# untitled.net
KiCad netlist of a schematic drawn in EAGLE
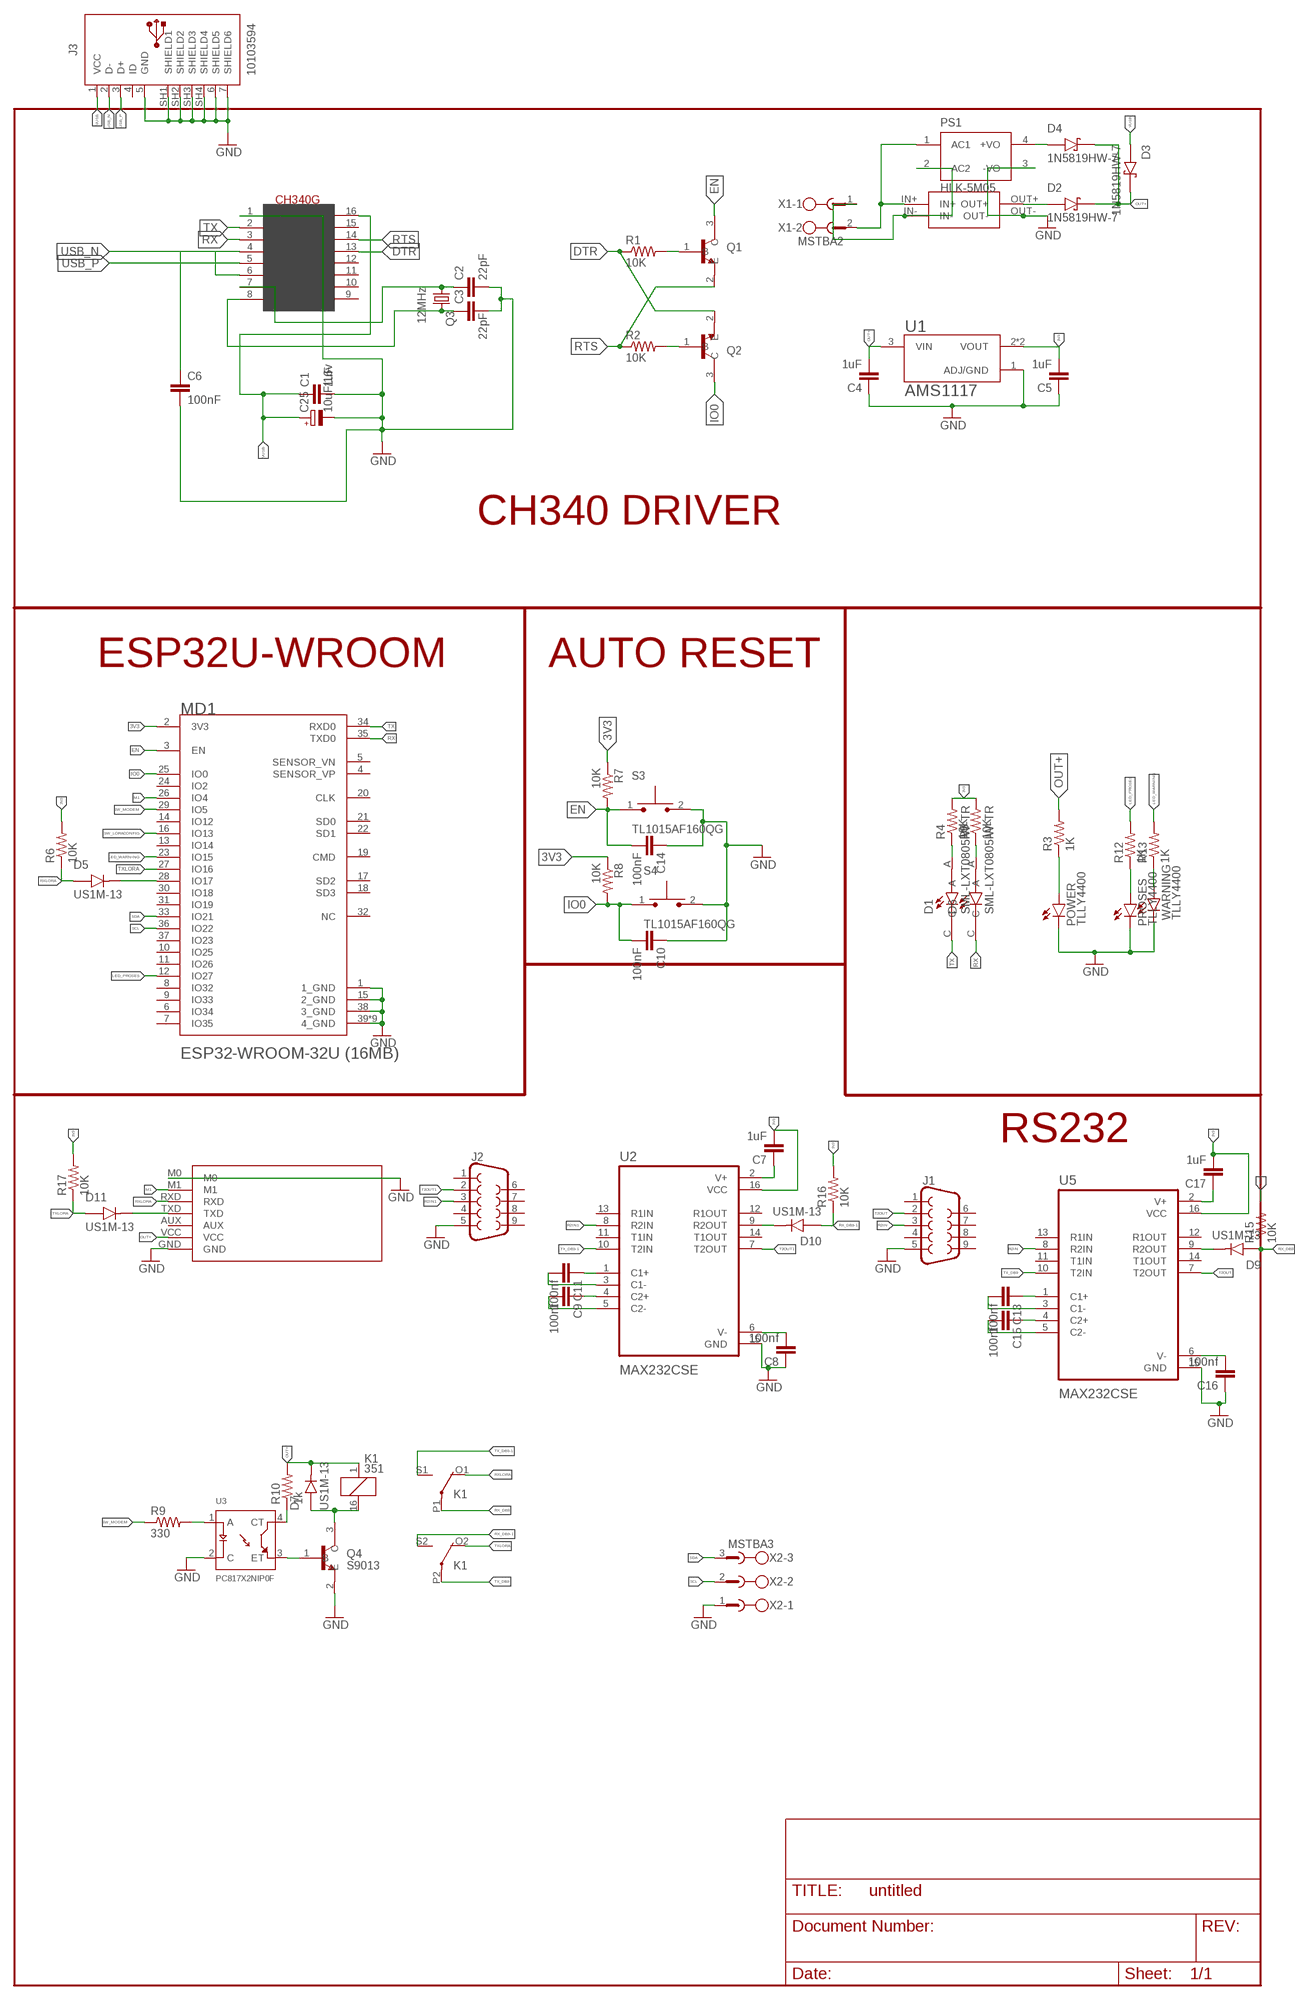
[diagram p0: schematic, sheet 1]

(export (version "E")
  (design (tool "Eeschema 10.0.6"))
  (components
    (comp (ref "C1")
      (value "1uF")
      (footprint "eagle-import:C0805K")
      (libsource (lib "eagle-import") (part "C-EUC0805K"))
    )
    (comp (ref "C2")
      (value "22pF")
      (footprint "eagle-import:C0805K")
      (libsource (lib "eagle-import") (part "C-EUC0805K"))
    )
    (comp (ref "C3")
      (value "22pF")
      (footprint "eagle-import:C0805K")
      (libsource (lib "eagle-import") (part "C-EUC0805K"))
    )
    (comp (ref "C4")
      (value "1uF")
      (footprint "eagle-import:C0805K")
      (libsource (lib "eagle-import") (part "C-EUC0805K"))
    )
    (comp (ref "C5")
      (value "1uF")
      (footprint "eagle-import:C0805K")
      (libsource (lib "eagle-import") (part "C-EUC0805K"))
    )
    (comp (ref "C6")
      (value "100nF")
      (footprint "eagle-import:C0805K")
      (libsource (lib "eagle-import") (part "C-EUC0805K"))
    )
    (comp (ref "C7")
      (value "1uF")
      (footprint "eagle-import:C0805")
      (libsource (lib "eagle-import") (part "C-EUC0805"))
    )
    (comp (ref "C8")
      (value "100nf")
      (footprint "eagle-import:C0805")
      (libsource (lib "eagle-import") (part "C-EUC0805"))
    )
    (comp (ref "C9")
      (value "100nf")
      (footprint "eagle-import:C0805")
      (libsource (lib "eagle-import") (part "C-EUC0805"))
    )
    (comp (ref "C10")
      (value "100nF")
      (footprint "eagle-import:C0805K")
      (libsource (lib "eagle-import") (part "C-EUC0805K"))
    )
    (comp (ref "C11")
      (value "100nf")
      (footprint "eagle-import:C0805")
      (libsource (lib "eagle-import") (part "C-EUC0805"))
    )
    (comp (ref "C13")
      (value "100nf")
      (footprint "eagle-import:C0805")
      (libsource (lib "eagle-import") (part "C-EUC0805"))
    )
    (comp (ref "C14")
      (value "100nF")
      (footprint "eagle-import:C0805K")
      (libsource (lib "eagle-import") (part "C-EUC0805K"))
    )
    (comp (ref "C15")
      (value "100nf")
      (footprint "eagle-import:C0805")
      (libsource (lib "eagle-import") (part "C-EUC0805"))
    )
    (comp (ref "C16")
      (value "100nf")
      (footprint "eagle-import:C0805")
      (libsource (lib "eagle-import") (part "C-EUC0805"))
    )
    (comp (ref "C17")
      (value "1uF")
      (footprint "eagle-import:C0805")
      (libsource (lib "eagle-import") (part "C-EUC0805"))
    )
    (comp (ref "C25")
      (value "10uF/16v")
      (footprint "eagle-import:153CLV-0505")
      (libsource (lib "eagle-import") (part "CPOL-EU153CLV-0505"))
    )
    (comp (ref "D1")
      (value "SML-LXT0805IW-TR")
      (footprint "eagle-import:LEDC2012X120N")
      (fields (field (name "MF") "Lumex Opto/Components"))
      (libsource (lib "eagle-import") (part "SML-LXT0805IW-TR"))
    )
    (comp (ref "D2")
      (value "1N5819HW-7")
      (footprint "eagle-import:SOD3715X145N")
      (fields (field (name "MF") "Diodes Inc."))
      (libsource (lib "eagle-import") (part "1N5819HW-7"))
    )
    (comp (ref "D3")
      (value "1N5819HW-7")
      (footprint "eagle-import:SOD3715X145N")
      (fields (field (name "MF") "Diodes Inc."))
      (libsource (lib "eagle-import") (part "1N5819HW-7"))
    )
    (comp (ref "D4")
      (value "1N5819HW-7")
      (footprint "eagle-import:SOD3715X145N")
      (fields (field (name "MF") "Diodes Inc."))
      (libsource (lib "eagle-import") (part "1N5819HW-7"))
    )
    (comp (ref "D5")
      (value "US1M-13")
      (footprint "eagle-import:DIOM5226X240N")
      (fields (field (name "MF") "Diodes Incorporated"))
      (libsource (lib "eagle-import") (part "US1M-13"))
    )
    (comp (ref "D6")
      (value "SML-LXT0805IW-TR")
      (footprint "eagle-import:LEDC2012X120N")
      (fields (field (name "MF") "Lumex Opto/Components"))
      (libsource (lib "eagle-import") (part "SML-LXT0805IW-TR"))
    )
    (comp (ref "D7")
      (value "US1M-13")
      (footprint "eagle-import:DIOM5226X240N")
      (fields (field (name "MF") "Diodes Incorporated"))
      (libsource (lib "eagle-import") (part "US1M-13"))
    )
    (comp (ref "D9")
      (value "US1M-13")
      (footprint "eagle-import:DIOM5226X240N")
      (fields (field (name "MF") "Diodes Incorporated"))
      (libsource (lib "eagle-import") (part "US1M-13"))
    )
    (comp (ref "D10")
      (value "US1M-13")
      (footprint "eagle-import:DIOM5226X240N")
      (fields (field (name "MF") "Diodes Incorporated"))
      (libsource (lib "eagle-import") (part "US1M-13"))
    )
    (comp (ref "D11")
      (value "US1M-13")
      (footprint "eagle-import:DIOM5226X240N")
      (fields (field (name "MF") "Diodes Incorporated"))
      (libsource (lib "eagle-import") (part "US1M-13"))
    )
    (comp (ref "EBYTEE220-900T22D1")
      (value "EBYTEE220-900T22D")
      (footprint "eagle-import:EBYTEE220-900T22D")
      (libsource (lib "eagle-import") (part "EBYTEE220-900T22D"))
    )
    (comp (ref "J1")
      (value "DB9MALE")
      (footprint "eagle-import:DB9_MALE")
      (libsource (lib "eagle-import") (part "DB9MALE"))
    )
    (comp (ref "J2")
      (value "DB9MALE")
      (footprint "eagle-import:DB9_MALE")
      (libsource (lib "eagle-import") (part "DB9MALE"))
    )
    (comp (ref "J3")
      (value "10103594")
      (footprint "eagle-import:10103594")
      (fields (field (name "MANUFACTURER") "Amphenol ICC (FCI)") (field (name "MPN") "10103594-0001LF"))
      (libsource (lib "eagle-import") (part "10103594"))
    )
    (comp (ref "K1")
      (value "351")
      (footprint "eagle-import:351")
      (libsource (lib "eagle-import") (part "351"))
    )
    (comp (ref "MD1")
      (value "ESPRESSIF_SYSTEMS_ESP32-WROOM-32U_16MBESPRESSIF_SYSTEMS_ESP32-WROOM-32U_16MB_0_0")
      (footprint "eagle-import:ESPRESSIF_SYSTEMS_ESP32-WROOM-32U_16MB_0")
      (fields
        (field (name "DIGIKEY_PART_NUMBER") "1904-1028-1-ND")
        (field (name "MF") "Espressif Systems")
        (field (name "MOUSER_PART_NUMBER") "356-ES32WROOM32U16MB")
      )
      (libsource (lib "eagle-import") (part "ESPRESSIF_SYSTEMS_ESP32-WROOM-32U_16MBESPRESSIF_SYSTEMS_ESP32-WROOM-32U_16MB_0_0"))
    )
    (comp (ref "MINI1")
      (value "MINI560")
      (footprint "eagle-import:MINI560")
      (libsource (lib "eagle-import") (part "MINI560"))
    )
    (comp (ref "POWER")
      (value "TLLY4400")
      (footprint "eagle-import:LED3MM")
      (fields (field (name "MF") "VISHAY SEMICONDUCTOR"))
      (libsource (lib "eagle-import") (part "TLLY4400"))
    )
    (comp (ref "PROSES")
      (value "TLLY4400")
      (footprint "eagle-import:LED3MM")
      (fields (field (name "MF") "VISHAY SEMICONDUCTOR"))
      (libsource (lib "eagle-import") (part "TLLY4400"))
    )
    (comp (ref "PS1")
      (value "HLK-5M05")
      (footprint "eagle-import:CONV_HLK-5M05")
      (fields (field (name "MF") "Hi-link"))
      (libsource (lib "eagle-import") (part "HLK-5M05"))
    )
    (comp (ref "Q1")
      (value "MMBT3904")
      (footprint "eagle-import:SOT95P240X120-3N")
      (fields (field (name "MF") "STMicroelectronics"))
      (libsource (lib "eagle-import") (part "MMBT3904"))
    )
    (comp (ref "Q2")
      (value "MMBT3904")
      (footprint "eagle-import:SOT95P240X120-3N")
      (fields (field (name "MF") "STMicroelectronics"))
      (libsource (lib "eagle-import") (part "MMBT3904"))
    )
    (comp (ref "Q3")
      (value "12MHz")
      (footprint "eagle-import:SM49")
      (libsource (lib "eagle-import") (part "CRYSTALSM49"))
    )
    (comp (ref "Q4")
      (value "S9013")
      (footprint "eagle-import:SOT95P240X120-3N")
      (fields (field (name "MF") "JCET"))
      (libsource (lib "eagle-import") (part "S9013"))
    )
    (comp (ref "R1")
      (value "10K")
      (footprint "eagle-import:M0805")
      (libsource (lib "eagle-import") (part "R-US_M0805"))
    )
    (comp (ref "R2")
      (value "10K")
      (footprint "eagle-import:M0805")
      (libsource (lib "eagle-import") (part "R-US_M0805"))
    )
    (comp (ref "R3")
      (value "1K")
      (footprint "eagle-import:M0805")
      (libsource (lib "eagle-import") (part "R-US_M0805"))
    )
    (comp (ref "R4")
      (value "10K")
      (footprint "eagle-import:M0805")
      (libsource (lib "eagle-import") (part "R-US_M0805"))
    )
    (comp (ref "R5")
      (value "10K")
      (footprint "eagle-import:M0805")
      (libsource (lib "eagle-import") (part "R-US_M0805"))
    )
    (comp (ref "R6")
      (value "10K")
      (footprint "eagle-import:M0805")
      (libsource (lib "eagle-import") (part "R-US_M0805"))
    )
    (comp (ref "R7")
      (value "10K")
      (footprint "eagle-import:M0805")
      (libsource (lib "eagle-import") (part "R-US_M0805"))
    )
    (comp (ref "R8")
      (value "10K")
      (footprint "eagle-import:M0805")
      (libsource (lib "eagle-import") (part "R-US_M0805"))
    )
    (comp (ref "R9")
      (value "330")
      (footprint "eagle-import:M0805")
      (libsource (lib "eagle-import") (part "R-US_M0805"))
    )
    (comp (ref "R10")
      (value "1k")
      (footprint "eagle-import:M0805")
      (libsource (lib "eagle-import") (part "R-US_M0805"))
    )
    (comp (ref "R12")
      (value "1K")
      (footprint "eagle-import:M0805")
      (libsource (lib "eagle-import") (part "R-US_M0805"))
    )
    (comp (ref "R13")
      (value "1K")
      (footprint "eagle-import:M0805")
      (libsource (lib "eagle-import") (part "R-US_M0805"))
    )
    (comp (ref "R15")
      (value "10K")
      (footprint "eagle-import:M0805")
      (libsource (lib "eagle-import") (part "R-US_M0805"))
    )
    (comp (ref "R16")
      (value "10K")
      (footprint "eagle-import:M0805")
      (libsource (lib "eagle-import") (part "R-US_M0805"))
    )
    (comp (ref "R17")
      (value "10K")
      (footprint "eagle-import:M0805")
      (libsource (lib "eagle-import") (part "R-US_M0805"))
    )
    (comp (ref "S3")
      (value "TL1015AF160QG")
      (footprint "eagle-import:SW_TL1015AF160QG")
      (fields (field (name "MF") "E-Switch"))
      (libsource (lib "eagle-import") (part "TL1015AF160QG"))
    )
    (comp (ref "S4")
      (value "TL1015AF160QG")
      (footprint "eagle-import:SW_TL1015AF160QG")
      (fields (field (name "MF") "E-Switch"))
      (libsource (lib "eagle-import") (part "TL1015AF160QG"))
    )
    (comp (ref "U$2")
      (value "CH340G")
      (footprint "eagle-import:SOIC16")
      (libsource (lib "eagle-import") (part "CH340G"))
    )
    (comp (ref "U1")
      (value "AMS1117")
      (footprint "eagle-import:SOT229P700X180-4N")
      (fields (field (name "MF") "Advanced Monolithic Systems"))
      (libsource (lib "eagle-import") (part "AMS1117"))
    )
    (comp (ref "U2")
      (value "MAX232CSE")
      (footprint "eagle-import:SOIC127P600X175-16N")
      (fields (field (name "MF") "Maxim Integrated"))
      (libsource (lib "eagle-import") (part "MAX232CSE"))
    )
    (comp (ref "U3")
      (value "PC817X2NIP0F")
      (footprint "eagle-import:SOT254P975X400-4N")
      (fields (field (name "MF") "Sharp Microelectronics"))
      (libsource (lib "eagle-import") (part "PC817X2NIP0F"))
    )
    (comp (ref "U5")
      (value "MAX232CSE")
      (footprint "eagle-import:SOIC127P600X175-16N")
      (fields (field (name "MF") "Maxim Integrated"))
      (libsource (lib "eagle-import") (part "MAX232CSE"))
    )
    (comp (ref "WARNING")
      (value "TLLY4400")
      (footprint "eagle-import:LED3MM")
      (fields (field (name "MF") "VISHAY SEMICONDUCTOR"))
      (libsource (lib "eagle-import") (part "TLLY4400"))
    )
    (comp (ref "X1")
      (value "MSTBA2")
      (footprint "eagle-import:MSTBA2")
      (fields (field (name "MF") "FARNELL") (field (name "MPN") "1757242"))
      (libsource (lib "eagle-import") (part "MSTBA2"))
    )
    (comp (ref "X2")
      (value "MSTBA3")
      (footprint "eagle-import:MSTBA3")
      (fields (field (name "MF") "FARNELL") (field (name "MPN") "1757255"))
      (libsource (lib "eagle-import") (part "MSTBA3"))
    )
  )
  (nets
    (net (code "1") (name "3V3") (class "Default")
      (node (ref "C17") (pin "2") (pinfunction "2_2") (pintype "passive"))
      (node (ref "C5") (pin "2") (pinfunction "2_2") (pintype "passive"))
      (node (ref "C7") (pin "2") (pinfunction "2_2") (pintype "passive"))
      (node (ref "MD1") (pin "2") (pinfunction "3V3_2") (pintype "power_in"))
      (node (ref "R15") (pin "2") (pinfunction "2_2") (pintype "passive"))
      (node (ref "R16") (pin "2") (pinfunction "2_2") (pintype "passive"))
      (node (ref "R17") (pin "2") (pinfunction "2_2") (pintype "passive"))
      (node (ref "R4") (pin "2") (pinfunction "2_2") (pintype "passive"))
      (node (ref "R5") (pin "2") (pinfunction "2_2") (pintype "passive"))
      (node (ref "R6") (pin "2") (pinfunction "2_2") (pintype "passive"))
      (node (ref "R7") (pin "1") (pinfunction "1_1") (pintype "passive"))
      (node (ref "R8") (pin "1") (pinfunction "1_1") (pintype "passive"))
      (node (ref "U1") (pin "2") (pinfunction "VOUT_2") (pintype "output"))
      (node (ref "U1") (pin "4") (pinfunction "VOUT_4") (pintype "output"))
      (node (ref "U2") (pin "16") (pinfunction "VCC_16") (pintype "power_in"))
      (node (ref "U5") (pin "16") (pinfunction "VCC_16") (pintype "power_in"))
    )
    (net (code "2") (name "DTR") (class "Default")
      (node (ref "Q2") (pin "2") (pinfunction "E_2") (pintype "passive"))
      (node (ref "R1") (pin "1") (pinfunction "1_1") (pintype "passive"))
      (node (ref "U$2") (pin "13") (pinfunction "DTR_13") (pintype "bidirectional"))
    )
    (net (code "3") (name "EN") (class "Default")
      (node (ref "C14") (pin "2") (pinfunction "2_2") (pintype "passive"))
      (node (ref "MD1") (pin "3") (pinfunction "EN_3") (pintype "input"))
      (node (ref "Q1") (pin "3") (pinfunction "C_3") (pintype "passive"))
      (node (ref "R7") (pin "2") (pinfunction "2_2") (pintype "passive"))
      (node (ref "S3") (pin "1") (pinfunction "1_1") (pintype "passive"))
    )
    (net (code "4") (name "GND") (class "Default")
      (node (ref "C1") (pin "2") (pinfunction "2_2") (pintype "passive"))
      (node (ref "C10") (pin "1") (pinfunction "1_1") (pintype "passive"))
      (node (ref "C14") (pin "1") (pinfunction "1_1") (pintype "passive"))
      (node (ref "C16") (pin "1") (pinfunction "1_1") (pintype "passive"))
      (node (ref "C2") (pin "2") (pinfunction "2_2") (pintype "passive"))
      (node (ref "C25") (pin "-") (pinfunction "-_-") (pintype "passive"))
      (node (ref "C3") (pin "2") (pinfunction "2_2") (pintype "passive"))
      (node (ref "C4") (pin "1") (pinfunction "1_1") (pintype "passive"))
      (node (ref "C5") (pin "1") (pinfunction "1_1") (pintype "passive"))
      (node (ref "C6") (pin "2") (pinfunction "2_2") (pintype "passive"))
      (node (ref "C8") (pin "1") (pinfunction "1_1") (pintype "passive"))
      (node (ref "EBYTEE220-900T22D1") (pin "GND") (pinfunction "GND_GND") (pintype "bidirectional"))
      (node (ref "EBYTEE220-900T22D1") (pin "M0") (pinfunction "M0_M0") (pintype "bidirectional"))
      (node (ref "J1") (pin "5") (pinfunction "5_5") (pintype "passive"))
      (node (ref "J2") (pin "5") (pinfunction "5_5") (pintype "passive"))
      (node (ref "J3") (pin "5") (pinfunction "GND_5") (pintype "power_in"))
      (node (ref "J3") (pin "6") (pinfunction "SHIELD5_6") (pintype "power_in"))
      (node (ref "J3") (pin "7") (pinfunction "SHIELD6_7") (pintype "power_in"))
      (node (ref "J3") (pin "SH1") (pinfunction "SHIELD1_SH1") (pintype "power_in"))
      (node (ref "J3") (pin "SH2") (pinfunction "SHIELD2_SH2") (pintype "power_in"))
      (node (ref "J3") (pin "SH3") (pinfunction "SHIELD3_SH3") (pintype "power_in"))
      (node (ref "J3") (pin "SH4") (pinfunction "SHIELD4_SH4") (pintype "power_in"))
      (node (ref "MD1") (pin "1") (pinfunction "1_GND_1") (pintype "power_in"))
      (node (ref "MD1") (pin "15") (pinfunction "2_GND_15") (pintype "power_in"))
      (node (ref "MD1") (pin "38") (pinfunction "3_GND_38") (pintype "power_in"))
      (node (ref "MD1") (pin "39") (pinfunction "4_GND_39") (pintype "power_in"))
      (node (ref "MD1") (pin "39-2") (pinfunction "4_GND_39-2") (pintype "power_in"))
      (node (ref "MD1") (pin "39-3") (pinfunction "4_GND_39-3") (pintype "power_in"))
      (node (ref "MD1") (pin "39-4") (pinfunction "4_GND_39-4") (pintype "power_in"))
      (node (ref "MD1") (pin "39-5") (pinfunction "4_GND_39-5") (pintype "power_in"))
      (node (ref "MD1") (pin "39-6") (pinfunction "4_GND_39-6") (pintype "power_in"))
      (node (ref "MD1") (pin "39-7") (pinfunction "4_GND_39-7") (pintype "power_in"))
      (node (ref "MD1") (pin "39-8") (pinfunction "4_GND_39-8") (pintype "power_in"))
      (node (ref "MD1") (pin "39-9") (pinfunction "4_GND_39-9") (pintype "power_in"))
      (node (ref "MINI1") (pin "OUT-") (pinfunction "OUT-_OUT-") (pintype "bidirectional"))
      (node (ref "POWER") (pin "K") (pinfunction "C_K") (pintype "passive"))
      (node (ref "PROSES") (pin "K") (pinfunction "C_K") (pintype "passive"))
      (node (ref "PS1") (pin "3") (pinfunction "-VO_3") (pintype "output"))
      (node (ref "Q4") (pin "2") (pinfunction "E_2") (pintype "passive"))
      (node (ref "S3") (pin "2") (pinfunction "2_2") (pintype "passive"))
      (node (ref "S4") (pin "2") (pinfunction "2_2") (pintype "passive"))
      (node (ref "U$2") (pin "1") (pinfunction "GND_1") (pintype "bidirectional"))
      (node (ref "U1") (pin "1") (pinfunction "ADJ/GND_1") (pintype "power_in"))
      (node (ref "U2") (pin "15") (pinfunction "GND_15") (pintype "power_in"))
      (node (ref "U3") (pin "2") (pinfunction "C_2") (pintype "passive"))
      (node (ref "U5") (pin "15") (pinfunction "GND_15") (pintype "power_in"))
      (node (ref "WARNING") (pin "K") (pinfunction "C_K") (pintype "passive"))
      (node (ref "X2") (pin "1") (pinfunction "1_1") (pintype "passive"))
    )
    (net (code "5") (name "IO0") (class "Default")
      (node (ref "C10") (pin "2") (pinfunction "2_2") (pintype "passive"))
      (node (ref "MD1") (pin "25") (pinfunction "IO0_25") (pintype "bidirectional"))
      (node (ref "Q2") (pin "3") (pinfunction "C_3") (pintype "passive"))
      (node (ref "R8") (pin "2") (pinfunction "2_2") (pintype "passive"))
      (node (ref "S4") (pin "1") (pinfunction "1_1") (pintype "passive"))
    )
    (net (code "6") (name "LED_PROSES") (class "Default")
      (node (ref "MD1") (pin "12") (pinfunction "IO27_12") (pintype "bidirectional"))
      (node (ref "R12") (pin "2") (pinfunction "2_2") (pintype "passive"))
    )
    (net (code "7") (name "LED_WARNING") (class "Default")
      (node (ref "MD1") (pin "23") (pinfunction "IO15_23") (pintype "bidirectional"))
      (node (ref "R13") (pin "2") (pinfunction "2_2") (pintype "passive"))
    )
    (net (code "8") (name "M1") (class "Default")
      (node (ref "EBYTEE220-900T22D1") (pin "M1") (pinfunction "M1_M1") (pintype "bidirectional"))
      (node (ref "MD1") (pin "26") (pinfunction "IO4_26") (pintype "bidirectional"))
    )
    (net (code "9") (name "Net-(D1-PadA)") (class "Default")
      (node (ref "D1") (pin "A") (pinfunction "A_A") (pintype "passive"))
      (node (ref "R4") (pin "1") (pinfunction "1_1") (pintype "passive"))
    )
    (net (code "10") (name "Net-(D2-PadA)") (class "Default")
      (node (ref "D2") (pin "A") (pinfunction "A_A") (pintype "passive"))
      (node (ref "MINI1") (pin "OUT+") (pinfunction "OUT+_OUT+") (pintype "bidirectional"))
    )
    (net (code "11") (name "Net-(D5-K)") (class "Default")
      (node (ref "D5") (pin "C") (pinfunction "K_C") (pintype "passive"))
      (node (ref "MD1") (pin "28") (pinfunction "IO17_28") (pintype "bidirectional"))
    )
    (net (code "12") (name "Net-(D6-PadA)") (class "Default")
      (node (ref "D6") (pin "A") (pinfunction "A_A") (pintype "passive"))
      (node (ref "R5") (pin "1") (pinfunction "1_1") (pintype "passive"))
    )
    (net (code "13") (name "Net-(D9-K)") (class "Default")
      (node (ref "D9") (pin "C") (pinfunction "K_C") (pintype "passive"))
      (node (ref "U5") (pin "9") (pinfunction "R2OUT_9") (pintype "output"))
    )
    (net (code "14") (name "Net-(D10-K)") (class "Default")
      (node (ref "D10") (pin "C") (pinfunction "K_C") (pintype "passive"))
      (node (ref "U2") (pin "9") (pinfunction "R2OUT_9") (pintype "output"))
    )
    (net (code "15") (name "Net-(D11-K)") (class "Default")
      (node (ref "D11") (pin "C") (pinfunction "K_C") (pintype "passive"))
      (node (ref "EBYTEE220-900T22D1") (pin "TXD") (pinfunction "TXD_TXD") (pintype "bidirectional"))
    )
    (net (code "16") (name "Net-(K1A-2)") (class "Default")
      (node (ref "D7") (pin "A") (pinfunction "A_A") (pintype "passive"))
      (node (ref "K1") (pin "16") (pinfunction "2_16") (pintype "passive"))
      (node (ref "Q4") (pin "3") (pinfunction "C_3") (pintype "passive"))
    )
    (net (code "17") (name "Net-(POWER-PadA)") (class "Default")
      (node (ref "POWER") (pin "A") (pinfunction "A_A") (pintype "passive"))
      (node (ref "R3") (pin "1") (pinfunction "1_1") (pintype "passive"))
    )
    (net (code "18") (name "Net-(PROSES-PadA)") (class "Default")
      (node (ref "PROSES") (pin "A") (pinfunction "A_A") (pintype "passive"))
      (node (ref "R12") (pin "1") (pinfunction "1_1") (pintype "passive"))
    )
    (net (code "19") (name "Net-(PS1-+VO)") (class "Default")
      (node (ref "D4") (pin "A") (pinfunction "A_A") (pintype "passive"))
      (node (ref "PS1") (pin "4") (pinfunction "+VO_4") (pintype "output"))
    )
    (net (code "20") (name "Net-(PS1-AC1)") (class "Default")
      (node (ref "MINI1") (pin "IN+") (pinfunction "IN+_IN+") (pintype "bidirectional"))
      (node (ref "PS1") (pin "1") (pinfunction "AC1_1") (pintype "input"))
      (node (ref "X1") (pin "2") (pinfunction "1_2") (pintype "passive"))
    )
    (net (code "21") (name "Net-(PS1-AC2)") (class "Default")
      (node (ref "MINI1") (pin "IN-") (pinfunction "IN-_IN-") (pintype "bidirectional"))
      (node (ref "PS1") (pin "2") (pinfunction "AC2_2") (pintype "input"))
      (node (ref "X1") (pin "1") (pinfunction "1_1") (pintype "passive"))
    )
    (net (code "22") (name "Net-(Q1-B)") (class "Default")
      (node (ref "Q1") (pin "1") (pinfunction "B_1") (pintype "passive"))
      (node (ref "R1") (pin "2") (pinfunction "2_2") (pintype "passive"))
    )
    (net (code "23") (name "Net-(Q2-B)") (class "Default")
      (node (ref "Q2") (pin "1") (pinfunction "B_1") (pintype "passive"))
      (node (ref "R2") (pin "2") (pinfunction "2_2") (pintype "passive"))
    )
    (net (code "24") (name "Net-(Q4-B)") (class "Default")
      (node (ref "Q4") (pin "1") (pinfunction "B_1") (pintype "passive"))
      (node (ref "U3") (pin "3") (pinfunction "ET_3") (pintype "passive"))
    )
    (net (code "25") (name "Net-(R13-Pad1)") (class "Default")
      (node (ref "R13") (pin "1") (pinfunction "1_1") (pintype "passive"))
      (node (ref "WARNING") (pin "A") (pinfunction "A_A") (pintype "passive"))
    )
    (net (code "26") (name "Net-(U$2-V3)") (class "Default")
      (node (ref "C6") (pin "1") (pinfunction "1_1") (pintype "passive"))
      (node (ref "U$2") (pin "4") (pinfunction "V3_4") (pintype "bidirectional"))
    )
    (net (code "27") (name "Net-(U$2-XI)") (class "Default")
      (node (ref "C2") (pin "1") (pinfunction "1_1") (pintype "passive"))
      (node (ref "Q3") (pin "1") (pinfunction "1_1") (pintype "passive"))
      (node (ref "U$2") (pin "7") (pinfunction "XI_7") (pintype "bidirectional"))
    )
    (net (code "28") (name "Net-(U$2-XO)") (class "Default")
      (node (ref "C3") (pin "1") (pinfunction "1_1") (pintype "passive"))
      (node (ref "Q3") (pin "2") (pinfunction "2_2") (pintype "passive"))
      (node (ref "U$2") (pin "8") (pinfunction "XO_8") (pintype "bidirectional"))
    )
    (net (code "29") (name "Net-(U2-C1+)") (class "Default")
      (node (ref "C11") (pin "1") (pinfunction "1_1") (pintype "passive"))
      (node (ref "U2") (pin "1") (pinfunction "C1+_1") (pintype "bidirectional"))
    )
    (net (code "30") (name "Net-(U2-C1-)") (class "Default")
      (node (ref "C11") (pin "2") (pinfunction "2_2") (pintype "passive"))
      (node (ref "U2") (pin "3") (pinfunction "C1-_3") (pintype "bidirectional"))
    )
    (net (code "31") (name "Net-(U2-C2+)") (class "Default")
      (node (ref "C9") (pin "1") (pinfunction "1_1") (pintype "passive"))
      (node (ref "U2") (pin "4") (pinfunction "C2+_4") (pintype "bidirectional"))
    )
    (net (code "32") (name "Net-(U2-C2-)") (class "Default")
      (node (ref "C9") (pin "2") (pinfunction "2_2") (pintype "passive"))
      (node (ref "U2") (pin "5") (pinfunction "C2-_5") (pintype "bidirectional"))
    )
    (net (code "33") (name "Net-(U2-V+)") (class "Default")
      (node (ref "C7") (pin "1") (pinfunction "1_1") (pintype "passive"))
      (node (ref "U2") (pin "2") (pinfunction "V+_2") (pintype "power_in"))
    )
    (net (code "34") (name "Net-(U2-V-)") (class "Default")
      (node (ref "C8") (pin "2") (pinfunction "2_2") (pintype "passive"))
      (node (ref "U2") (pin "6") (pinfunction "V-_6") (pintype "power_in"))
    )
    (net (code "35") (name "Net-(U3-A)") (class "Default")
      (node (ref "R9") (pin "2") (pinfunction "2_2") (pintype "passive"))
      (node (ref "U3") (pin "1") (pinfunction "A_1") (pintype "passive"))
    )
    (net (code "36") (name "Net-(U3-CT)") (class "Default")
      (node (ref "R10") (pin "1") (pinfunction "1_1") (pintype "passive"))
      (node (ref "U3") (pin "4") (pinfunction "CT_4") (pintype "passive"))
    )
    (net (code "37") (name "Net-(U5-C1+)") (class "Default")
      (node (ref "C13") (pin "1") (pinfunction "1_1") (pintype "passive"))
      (node (ref "U5") (pin "1") (pinfunction "C1+_1") (pintype "bidirectional"))
    )
    (net (code "38") (name "Net-(U5-C1-)") (class "Default")
      (node (ref "C13") (pin "2") (pinfunction "2_2") (pintype "passive"))
      (node (ref "U5") (pin "3") (pinfunction "C1-_3") (pintype "bidirectional"))
    )
    (net (code "39") (name "Net-(U5-C2+)") (class "Default")
      (node (ref "C15") (pin "1") (pinfunction "1_1") (pintype "passive"))
      (node (ref "U5") (pin "4") (pinfunction "C2+_4") (pintype "bidirectional"))
    )
    (net (code "40") (name "Net-(U5-C2-)") (class "Default")
      (node (ref "C15") (pin "2") (pinfunction "2_2") (pintype "passive"))
      (node (ref "U5") (pin "5") (pinfunction "C2-_5") (pintype "bidirectional"))
    )
    (net (code "41") (name "Net-(U5-V+)") (class "Default")
      (node (ref "C17") (pin "1") (pinfunction "1_1") (pintype "passive"))
      (node (ref "U5") (pin "2") (pinfunction "V+_2") (pintype "power_in"))
    )
    (net (code "42") (name "Net-(U5-V-)") (class "Default")
      (node (ref "C16") (pin "2") (pinfunction "2_2") (pintype "passive"))
      (node (ref "U5") (pin "6") (pinfunction "V-_6") (pintype "power_in"))
    )
    (net (code "43") (name "OUT+") (class "Default")
      (node (ref "C4") (pin "2") (pinfunction "2_2") (pintype "passive"))
      (node (ref "D2") (pin "C") (pinfunction "K_C") (pintype "passive"))
      (node (ref "D3") (pin "C") (pinfunction "K_C") (pintype "passive"))
      (node (ref "D4") (pin "C") (pinfunction "K_C") (pintype "passive"))
      (node (ref "D7") (pin "C") (pinfunction "K_C") (pintype "passive"))
      (node (ref "EBYTEE220-900T22D1") (pin "VCC") (pinfunction "VCC_VCC") (pintype "bidirectional"))
      (node (ref "K1") (pin "1") (pinfunction "1_1") (pintype "passive"))
      (node (ref "R10") (pin "2") (pinfunction "2_2") (pintype "passive"))
      (node (ref "R3") (pin "2") (pinfunction "2_2") (pintype "passive"))
      (node (ref "U1") (pin "3") (pinfunction "VIN_3") (pintype "input"))
    )
    (net (code "44") (name "R2IN") (class "Default")
      (node (ref "J1") (pin "3") (pinfunction "3_3") (pintype "passive"))
      (node (ref "U5") (pin "8") (pinfunction "R2IN_8") (pintype "input"))
    )
    (net (code "45") (name "R2IN1") (class "Default")
      (node (ref "J2") (pin "3") (pinfunction "3_3") (pintype "passive"))
      (node (ref "U2") (pin "8") (pinfunction "R2IN_8") (pintype "input"))
    )
    (net (code "46") (name "RTS") (class "Default")
      (node (ref "Q1") (pin "2") (pinfunction "E_2") (pintype "passive"))
      (node (ref "R2") (pin "1") (pinfunction "1_1") (pintype "passive"))
      (node (ref "U$2") (pin "14") (pinfunction "RTS_14") (pintype "bidirectional"))
    )
    (net (code "47") (name "RX") (class "Default")
      (node (ref "D6") (pin "C") (pinfunction "C_C") (pintype "passive"))
      (node (ref "MD1") (pin "35") (pinfunction "TXD0_35") (pintype "bidirectional"))
      (node (ref "U$2") (pin "3") (pinfunction "RX_3") (pintype "bidirectional"))
    )
    (net (code "48") (name "RXLORA") (class "Default")
      (node (ref "D5") (pin "A") (pinfunction "A_A") (pintype "passive"))
      (node (ref "EBYTEE220-900T22D1") (pin "RXD") (pinfunction "RXD_RXD") (pintype "bidirectional"))
      (node (ref "K1") (pin "O1") (pinfunction "O_O1") (pintype "passive"))
      (node (ref "R6") (pin "1") (pinfunction "1_1") (pintype "passive"))
    )
    (net (code "49") (name "RX_DB9") (class "Default")
      (node (ref "D9") (pin "A") (pinfunction "A_A") (pintype "passive"))
      (node (ref "K1") (pin "P1") (pinfunction "P_P1") (pintype "passive"))
      (node (ref "R15") (pin "1") (pinfunction "1_1") (pintype "passive"))
    )
    (net (code "50") (name "RX_DB9-1") (class "Default")
      (node (ref "D10") (pin "A") (pinfunction "A_A") (pintype "passive"))
      (node (ref "K1") (pin "S2") (pinfunction "S_S2") (pintype "passive"))
      (node (ref "R16") (pin "1") (pinfunction "1_1") (pintype "passive"))
    )
    (net (code "51") (name "SCL") (class "Default")
      (node (ref "MD1") (pin "36") (pinfunction "IO22_36") (pintype "bidirectional"))
      (node (ref "X2") (pin "2") (pinfunction "1_2") (pintype "passive"))
    )
    (net (code "52") (name "SDA") (class "Default")
      (node (ref "MD1") (pin "33") (pinfunction "IO21_33") (pintype "bidirectional"))
      (node (ref "X2") (pin "3") (pinfunction "1_3") (pintype "passive"))
    )
    (net (code "53") (name "SW_LORACONFIG") (class "Default")
      (node (ref "MD1") (pin "16") (pinfunction "IO13_16") (pintype "bidirectional"))
    )
    (net (code "54") (name "SW_MODEM") (class "Default")
      (node (ref "MD1") (pin "29") (pinfunction "IO5_29") (pintype "bidirectional"))
      (node (ref "R9") (pin "1") (pinfunction "1_1") (pintype "passive"))
    )
    (net (code "55") (name "T2OUT") (class "Default")
      (node (ref "J1") (pin "2") (pinfunction "2_2") (pintype "passive"))
      (node (ref "U5") (pin "7") (pinfunction "T2OUT_7") (pintype "output"))
    )
    (net (code "56") (name "T2OUT1") (class "Default")
      (node (ref "J2") (pin "2") (pinfunction "2_2") (pintype "passive"))
      (node (ref "U2") (pin "7") (pinfunction "T2OUT_7") (pintype "output"))
    )
    (net (code "57") (name "TX") (class "Default")
      (node (ref "D1") (pin "C") (pinfunction "C_C") (pintype "passive"))
      (node (ref "MD1") (pin "34") (pinfunction "RXD0_34") (pintype "bidirectional"))
      (node (ref "U$2") (pin "2") (pinfunction "TX_2") (pintype "bidirectional"))
    )
    (net (code "58") (name "TXLORA") (class "Default")
      (node (ref "D11") (pin "A") (pinfunction "A_A") (pintype "passive"))
      (node (ref "K1") (pin "O2") (pinfunction "O_O2") (pintype "passive"))
      (node (ref "MD1") (pin "27") (pinfunction "IO16_27") (pintype "bidirectional"))
      (node (ref "R17") (pin "1") (pinfunction "1_1") (pintype "passive"))
    )
    (net (code "59") (name "TX_DB9") (class "Default")
      (node (ref "K1") (pin "P2") (pinfunction "P_P2") (pintype "passive"))
      (node (ref "U5") (pin "10") (pinfunction "T2IN_10") (pintype "input"))
    )
    (net (code "60") (name "TX_DB9-1") (class "Default")
      (node (ref "K1") (pin "S1") (pinfunction "S_S1") (pintype "passive"))
      (node (ref "U2") (pin "10") (pinfunction "T2IN_10") (pintype "input"))
    )
    (net (code "61") (name "USB_N") (class "Default")
      (node (ref "J3") (pin "2") (pinfunction "D-_2") (pintype "bidirectional"))
      (node (ref "U$2") (pin "6") (pinfunction "D-_6") (pintype "bidirectional"))
    )
    (net (code "62") (name "USB_P") (class "Default")
      (node (ref "J3") (pin "3") (pinfunction "D+_3") (pintype "bidirectional"))
      (node (ref "U$2") (pin "5") (pinfunction "D+_5") (pintype "bidirectional"))
    )
    (net (code "63") (name "VUSB") (class "Default")
      (node (ref "C1") (pin "1") (pinfunction "1_1") (pintype "passive"))
      (node (ref "C25") (pin "+") (pinfunction "+_+") (pintype "passive"))
      (node (ref "D3") (pin "A") (pinfunction "A_A") (pintype "passive"))
      (node (ref "J3") (pin "1") (pinfunction "VCC_1") (pintype "power_in"))
      (node (ref "U$2") (pin "16") (pinfunction "VCC_16") (pintype "bidirectional"))
    )
    (net (code "64") (name "unconnected-(EBYTEE220-900T22D1-PadAUX)") (class "Default")
      (node (ref "EBYTEE220-900T22D1") (pin "AUX") (pinfunction "AUX_AUX") (pintype "bidirectional"))
    )
    (net (code "65") (name "unconnected-(J1-Pad1)") (class "Default")
      (node (ref "J1") (pin "1") (pinfunction "1_1") (pintype "passive"))
    )
    (net (code "66") (name "unconnected-(J1-Pad4)") (class "Default")
      (node (ref "J1") (pin "4") (pinfunction "4_4") (pintype "passive"))
    )
    (net (code "67") (name "unconnected-(J1-Pad6)") (class "Default")
      (node (ref "J1") (pin "6") (pinfunction "6_6") (pintype "passive"))
    )
    (net (code "68") (name "unconnected-(J1-Pad7)") (class "Default")
      (node (ref "J1") (pin "7") (pinfunction "7_7") (pintype "passive"))
    )
    (net (code "69") (name "unconnected-(J1-Pad8)") (class "Default")
      (node (ref "J1") (pin "8") (pinfunction "8_8") (pintype "passive"))
    )
    (net (code "70") (name "unconnected-(J1-Pad9)") (class "Default")
      (node (ref "J1") (pin "9") (pinfunction "9_9") (pintype "passive"))
    )
    (net (code "71") (name "unconnected-(J2-Pad1)") (class "Default")
      (node (ref "J2") (pin "1") (pinfunction "1_1") (pintype "passive"))
    )
    (net (code "72") (name "unconnected-(J2-Pad4)") (class "Default")
      (node (ref "J2") (pin "4") (pinfunction "4_4") (pintype "passive"))
    )
    (net (code "73") (name "unconnected-(J2-Pad6)") (class "Default")
      (node (ref "J2") (pin "6") (pinfunction "6_6") (pintype "passive"))
    )
    (net (code "74") (name "unconnected-(J2-Pad7)") (class "Default")
      (node (ref "J2") (pin "7") (pinfunction "7_7") (pintype "passive"))
    )
    (net (code "75") (name "unconnected-(J2-Pad8)") (class "Default")
      (node (ref "J2") (pin "8") (pinfunction "8_8") (pintype "passive"))
    )
    (net (code "76") (name "unconnected-(J2-Pad9)") (class "Default")
      (node (ref "J2") (pin "9") (pinfunction "9_9") (pintype "passive"))
    )
    (net (code "77") (name "unconnected-(J3-ID-Pad4)") (class "Default")
      (node (ref "J3") (pin "4") (pinfunction "ID_4") (pintype "bidirectional"))
    )
    (net (code "78") (name "unconnected-(MD1-CLK-Pad20)") (class "Default")
      (node (ref "MD1") (pin "20") (pinfunction "CLK_20") (pintype "bidirectional"))
    )
    (net (code "79") (name "unconnected-(MD1-CMD-Pad19)") (class "Default")
      (node (ref "MD1") (pin "19") (pinfunction "CMD_19") (pintype "bidirectional"))
    )
    (net (code "80") (name "unconnected-(MD1-IO2-Pad24)") (class "Default")
      (node (ref "MD1") (pin "24") (pinfunction "IO2_24") (pintype "bidirectional"))
    )
    (net (code "81") (name "unconnected-(MD1-IO12-Pad14)") (class "Default")
      (node (ref "MD1") (pin "14") (pinfunction "IO12_14") (pintype "bidirectional"))
    )
    (net (code "82") (name "unconnected-(MD1-IO14-Pad13)") (class "Default")
      (node (ref "MD1") (pin "13") (pinfunction "IO14_13") (pintype "bidirectional"))
    )
    (net (code "83") (name "unconnected-(MD1-IO18-Pad30)") (class "Default")
      (node (ref "MD1") (pin "30") (pinfunction "IO18_30") (pintype "bidirectional"))
    )
    (net (code "84") (name "unconnected-(MD1-IO19-Pad31)") (class "Default")
      (node (ref "MD1") (pin "31") (pinfunction "IO19_31") (pintype "bidirectional"))
    )
    (net (code "85") (name "unconnected-(MD1-IO23-Pad37)") (class "Default")
      (node (ref "MD1") (pin "37") (pinfunction "IO23_37") (pintype "bidirectional"))
    )
    (net (code "86") (name "unconnected-(MD1-IO25-Pad10)") (class "Default")
      (node (ref "MD1") (pin "10") (pinfunction "IO25_10") (pintype "bidirectional"))
    )
    (net (code "87") (name "unconnected-(MD1-IO26-Pad11)") (class "Default")
      (node (ref "MD1") (pin "11") (pinfunction "IO26_11") (pintype "bidirectional"))
    )
    (net (code "88") (name "unconnected-(MD1-IO32-Pad8)") (class "Default")
      (node (ref "MD1") (pin "8") (pinfunction "IO32_8") (pintype "bidirectional"))
    )
    (net (code "89") (name "unconnected-(MD1-IO33-Pad9)") (class "Default")
      (node (ref "MD1") (pin "9") (pinfunction "IO33_9") (pintype "bidirectional"))
    )
    (net (code "90") (name "unconnected-(MD1-IO34-Pad6)") (class "Default")
      (node (ref "MD1") (pin "6") (pinfunction "IO34_6") (pintype "bidirectional"))
    )
    (net (code "91") (name "unconnected-(MD1-IO35-Pad7)") (class "Default")
      (node (ref "MD1") (pin "7") (pinfunction "IO35_7") (pintype "bidirectional"))
    )
    (net (code "92") (name "unconnected-(MD1-NC-Pad32)") (class "Default")
      (node (ref "MD1") (pin "32") (pinfunction "NC_32") (pintype "passive"))
    )
    (net (code "93") (name "unconnected-(MD1-SD0-Pad21)") (class "Default")
      (node (ref "MD1") (pin "21") (pinfunction "SD0_21") (pintype "bidirectional"))
    )
    (net (code "94") (name "unconnected-(MD1-SD1-Pad22)") (class "Default")
      (node (ref "MD1") (pin "22") (pinfunction "SD1_22") (pintype "bidirectional"))
    )
    (net (code "95") (name "unconnected-(MD1-SD2-Pad17)") (class "Default")
      (node (ref "MD1") (pin "17") (pinfunction "SD2_17") (pintype "bidirectional"))
    )
    (net (code "96") (name "unconnected-(MD1-SD3-Pad18)") (class "Default")
      (node (ref "MD1") (pin "18") (pinfunction "SD3_18") (pintype "bidirectional"))
    )
    (net (code "97") (name "unconnected-(MD1-SENSOR_VN-Pad5)") (class "Default")
      (node (ref "MD1") (pin "5") (pinfunction "SENSOR_VN_5") (pintype "input"))
    )
    (net (code "98") (name "unconnected-(MD1-SENSOR_VP-Pad4)") (class "Default")
      (node (ref "MD1") (pin "4") (pinfunction "SENSOR_VP_4") (pintype "input"))
    )
    (net (code "99") (name "unconnected-(U$2-CTS-Pad9)") (class "Default")
      (node (ref "U$2") (pin "9") (pinfunction "CTS_9") (pintype "bidirectional"))
    )
    (net (code "100") (name "unconnected-(U$2-DCD-Pad12)") (class "Default")
      (node (ref "U$2") (pin "12") (pinfunction "DCD_12") (pintype "bidirectional"))
    )
    (net (code "101") (name "unconnected-(U$2-DSR-Pad10)") (class "Default")
      (node (ref "U$2") (pin "10") (pinfunction "DSR_10") (pintype "bidirectional"))
    )
    (net (code "102") (name "unconnected-(U$2-RI-Pad11)") (class "Default")
      (node (ref "U$2") (pin "11") (pinfunction "RI_11") (pintype "bidirectional"))
    )
    (net (code "103") (name "unconnected-(U$2-RS232-Pad15)") (class "Default")
      (node (ref "U$2") (pin "15") (pinfunction "RS232_15") (pintype "bidirectional"))
    )
    (net (code "104") (name "unconnected-(U2-R1IN-Pad13)") (class "Default")
      (node (ref "U2") (pin "13") (pinfunction "R1IN_13") (pintype "input"))
    )
    (net (code "105") (name "unconnected-(U2-R1OUT-Pad12)") (class "Default")
      (node (ref "U2") (pin "12") (pinfunction "R1OUT_12") (pintype "output"))
    )
    (net (code "106") (name "unconnected-(U2-T1IN-Pad11)") (class "Default")
      (node (ref "U2") (pin "11") (pinfunction "T1IN_11") (pintype "input"))
    )
    (net (code "107") (name "unconnected-(U2-T1OUT-Pad14)") (class "Default")
      (node (ref "U2") (pin "14") (pinfunction "T1OUT_14") (pintype "output"))
    )
    (net (code "108") (name "unconnected-(U5-R1IN-Pad13)") (class "Default")
      (node (ref "U5") (pin "13") (pinfunction "R1IN_13") (pintype "input"))
    )
    (net (code "109") (name "unconnected-(U5-R1OUT-Pad12)") (class "Default")
      (node (ref "U5") (pin "12") (pinfunction "R1OUT_12") (pintype "output"))
    )
    (net (code "110") (name "unconnected-(U5-T1IN-Pad11)") (class "Default")
      (node (ref "U5") (pin "11") (pinfunction "T1IN_11") (pintype "input"))
    )
    (net (code "111") (name "unconnected-(U5-T1OUT-Pad14)") (class "Default")
      (node (ref "U5") (pin "14") (pinfunction "T1OUT_14") (pintype "output"))
    )
  )
)
